# CAN.net
KiCad netlist of a schematic drawn in Altium Designer
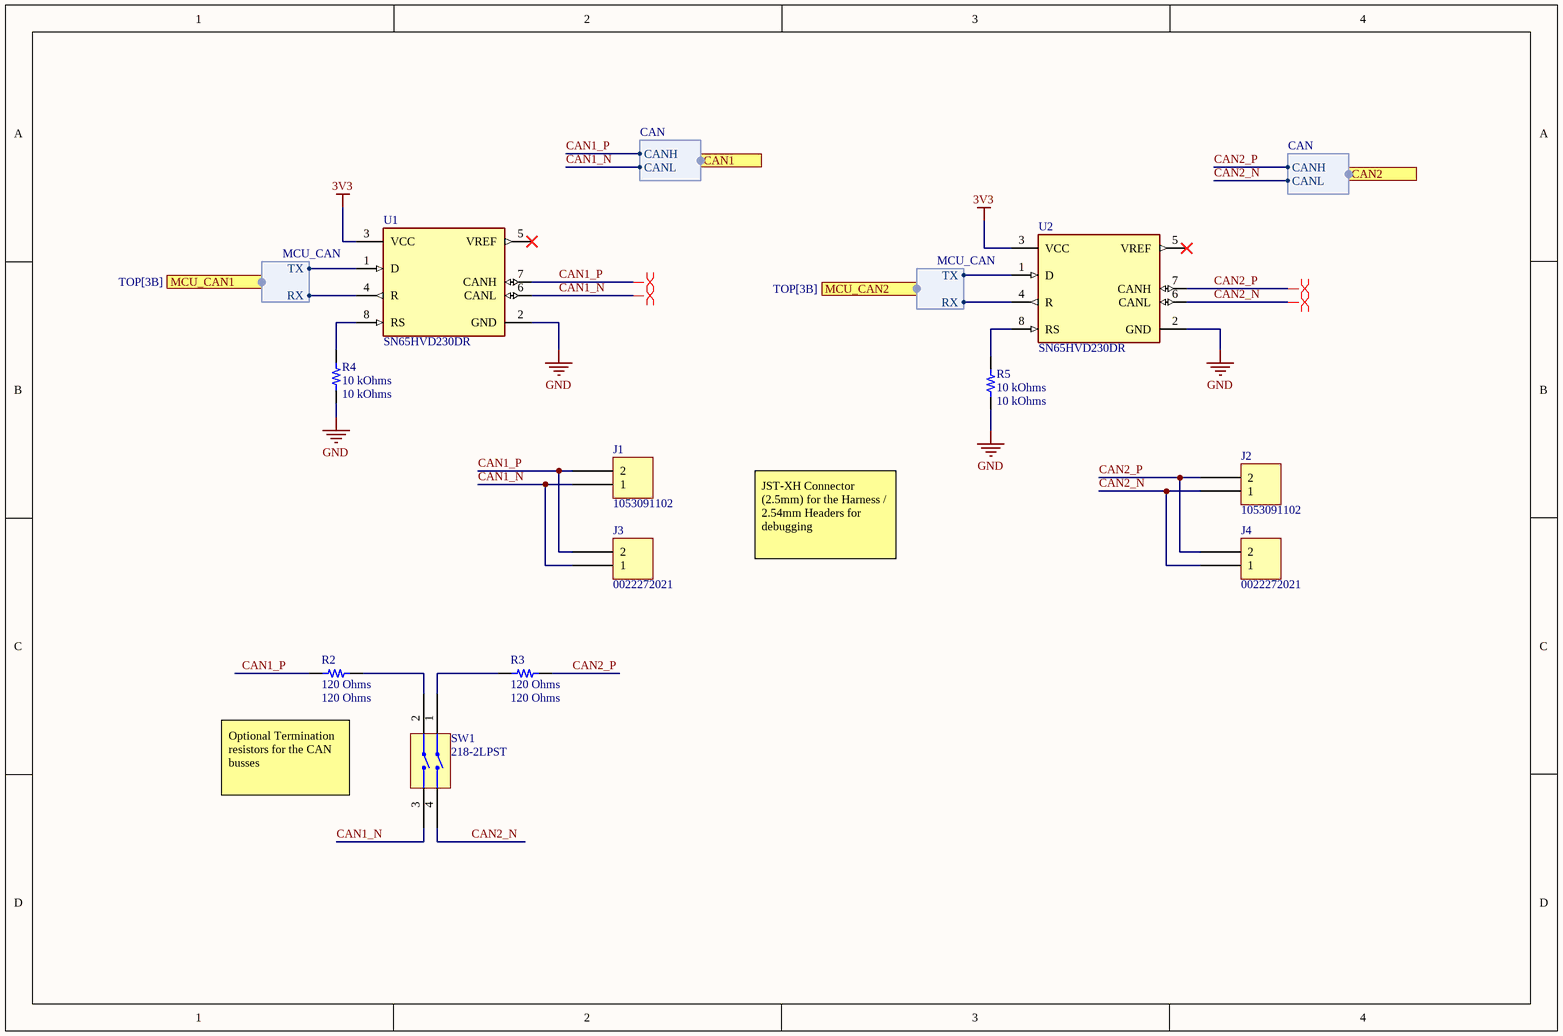
[diagram p0: CAN.SchDoc]

(export (version "E")
  (design (tool "Eeschema 10.0.6"))
  (components
    (comp (ref "J1")
      (value "1053091102")
      (footprint "MOLEX 1053091102")
      (description "CONN HEADER VERT 2POS 2.5MM")
      (libsource (lib "altium_library") (part "2 Pin"))
    )
    (comp (ref "J2")
      (value "1053091102")
      (footprint "MOLEX 1053091102")
      (description "CONN HEADER VERT 2POS 2.5MM")
      (libsource (lib "altium_library") (part "2 Pin"))
    )
    (comp (ref "J3")
      (value "0022272021")
      (footprint "MOLEX KK 0022272021")
      (description "CONN HEADER VERT 2POS 2.54MM")
      (libsource (lib "altium_library") (part "2 Pin"))
    )
    (comp (ref "J4")
      (value "0022272021")
      (footprint "MOLEX KK 0022272021")
      (description "CONN HEADER VERT 2POS 2.54MM")
      (libsource (lib "altium_library") (part "2 Pin"))
    )
    (comp (ref "R2")
      (value "120 Ohms")
      (footprint "RES 0603_1608")
      (description "RES SMD 120 OHM 0.1% 1/10W 0603")
      (fields (field (name "PART NUMBER") "ERA-3AEB121V") (field (name "ALTIUM_VALUE") "120 Ohms"))
      (libsource (lib "altium_library") (part "Resistor"))
    )
    (comp (ref "R3")
      (value "120 Ohms")
      (footprint "RES 0603_1608")
      (description "RES SMD 120 OHM 0.1% 1/10W 0603")
      (fields (field (name "PART NUMBER") "ERA-3AEB121V") (field (name "ALTIUM_VALUE") "120 Ohms"))
      (libsource (lib "altium_library") (part "Resistor"))
    )
    (comp (ref "R4")
      (value "10 kOhms")
      (footprint "RES 0603_1608")
      (description "RES SMD 10K OHM 1% 1/10W 0603")
      (fields (field (name "PART NUMBER") "AA0603FR-0710KL") (field (name "ALTIUM_VALUE") "10 kOhms"))
      (libsource (lib "altium_library") (part "Resistor"))
    )
    (comp (ref "R5")
      (value "10 kOhms")
      (footprint "RES 0603_1608")
      (description "RES SMD 10K OHM 1% 1/10W 0603")
      (fields (field (name "PART NUMBER") "AA0603FR-0710KL") (field (name "ALTIUM_VALUE") "10 kOhms"))
      (libsource (lib "altium_library") (part "Resistor"))
    )
    (comp (ref "SW1")
      (value "218-2LPST")
      (footprint "CTS 218-2LPJ")
      (description "SWITCH SLIDE DIP SPST 25MA 24V")
      (libsource (lib "altium_library") (part "DIP SW 2P"))
    )
    (comp (ref "U1")
      (value "SN65HVD230DR")
      (footprint "FP-D0008A-IPC_A")
      (description "IC TRANSCEIVER HALF 1/1 8SOIC")
      (libsource (lib "Altium Content Vault") (part "43b56812b1adf0e60a7acfb7c27ab91"))
    )
    (comp (ref "U2")
      (value "SN65HVD230DR")
      (footprint "FP-D0008A-IPC_A")
      (description "IC TRANSCEIVER HALF 1/1 8SOIC")
      (libsource (lib "Altium Content Vault") (part "43b56812b1adf0e60a7acfb7c27ab91"))
    )
  )
  (nets
    (net (code "3") (name "/CAN1_N") (class "Default")
      (node (ref "J1") (pin "1") (pinfunction "1_1") (pintype "passive"))
      (node (ref "J3") (pin "1") (pinfunction "1_1") (pintype "passive"))
      (node (ref "SW1") (pin "3") (pinfunction "GND_3") (pintype "passive"))
      (node (ref "U1") (pin "6") (pinfunction "CANL_6") (pintype "bidirectional"))
    )
    (net (code "4") (name "/CAN1_P") (class "Default")
      (node (ref "J1") (pin "2") (pinfunction "2_2") (pintype "passive"))
      (node (ref "J3") (pin "2") (pinfunction "2_2") (pintype "passive"))
      (node (ref "R2") (pin "1") (pinfunction "1_1") (pintype "passive"))
      (node (ref "U1") (pin "7") (pinfunction "CANH_7") (pintype "bidirectional"))
    )
    (net (code "5") (name "/CAN2_N") (class "Default")
      (node (ref "J2") (pin "1") (pinfunction "1_1") (pintype "passive"))
      (node (ref "J4") (pin "1") (pinfunction "1_1") (pintype "passive"))
      (node (ref "SW1") (pin "4") (pinfunction "GND_4") (pintype "passive"))
      (node (ref "U2") (pin "6") (pinfunction "CANL_6") (pintype "bidirectional"))
    )
    (net (code "6") (name "/CAN2_P") (class "Default")
      (node (ref "J2") (pin "2") (pinfunction "2_2") (pintype "passive"))
      (node (ref "J4") (pin "2") (pinfunction "2_2") (pintype "passive"))
      (node (ref "R3") (pin "2") (pinfunction "2_2") (pintype "passive"))
      (node (ref "U2") (pin "7") (pinfunction "CANH_7") (pintype "bidirectional"))
    )
    (net (code "9") (name "3V3") (class "Default")
      (node (ref "U1") (pin "3") (pinfunction "VCC_3") (pintype "power_in"))
      (node (ref "U2") (pin "3") (pinfunction "VCC_3") (pintype "power_in"))
    )
    (net (code "10") (name "GND") (class "Default")
      (node (ref "R4") (pin "1") (pinfunction "1_1") (pintype "passive"))
      (node (ref "R5") (pin "1") (pinfunction "1_1") (pintype "passive"))
      (node (ref "U1") (pin "2") (pinfunction "GND_2") (pintype "power_in"))
      (node (ref "U2") (pin "2") (pinfunction "GND_2") (pintype "power_in"))
    )
    (net (code "11") (name "Net-(R2-Pad2)") (class "Default")
      (node (ref "R2") (pin "2") (pinfunction "2_2") (pintype "passive"))
      (node (ref "SW1") (pin "2") (pinfunction "GND_2") (pintype "passive"))
    )
    (net (code "12") (name "Net-(R3-Pad1)") (class "Default")
      (node (ref "R3") (pin "1") (pinfunction "1_1") (pintype "passive"))
      (node (ref "SW1") (pin "1") (pinfunction "GND_1") (pintype "passive"))
    )
    (net (code "13") (name "Net-(U1-RS)") (class "Default")
      (node (ref "R4") (pin "2") (pinfunction "2_2") (pintype "passive"))
      (node (ref "U1") (pin "8") (pinfunction "RS_8") (pintype "input"))
    )
    (net (code "14") (name "Net-(U2-RS)") (class "Default")
      (node (ref "R5") (pin "2") (pinfunction "2_2") (pintype "passive"))
      (node (ref "U2") (pin "8") (pinfunction "RS_8") (pintype "input"))
    )
    (net (code "15") (name "unconnected-(U1-D-Pad1)") (class "Default")
      (node (ref "U1") (pin "1") (pinfunction "D_1") (pintype "input"))
    )
    (net (code "16") (name "unconnected-(U1-R-Pad4)") (class "Default")
      (node (ref "U1") (pin "4") (pinfunction "R_4") (pintype "output"))
    )
    (net (code "17") (name "unconnected-(U1-VREF-Pad5)") (class "Default")
      (node (ref "U1") (pin "5") (pinfunction "VREF_5") (pintype "output+no_connect"))
    )
    (net (code "18") (name "unconnected-(U2-D-Pad1)") (class "Default")
      (node (ref "U2") (pin "1") (pinfunction "D_1") (pintype "input"))
    )
    (net (code "19") (name "unconnected-(U2-R-Pad4)") (class "Default")
      (node (ref "U2") (pin "4") (pinfunction "R_4") (pintype "output"))
    )
    (net (code "20") (name "unconnected-(U2-VREF-Pad5)") (class "Default")
      (node (ref "U2") (pin "5") (pinfunction "VREF_5") (pintype "output+no_connect"))
    )
  )
)
